# LEDs.net
KiCad netlist of a schematic drawn in Altium Designer
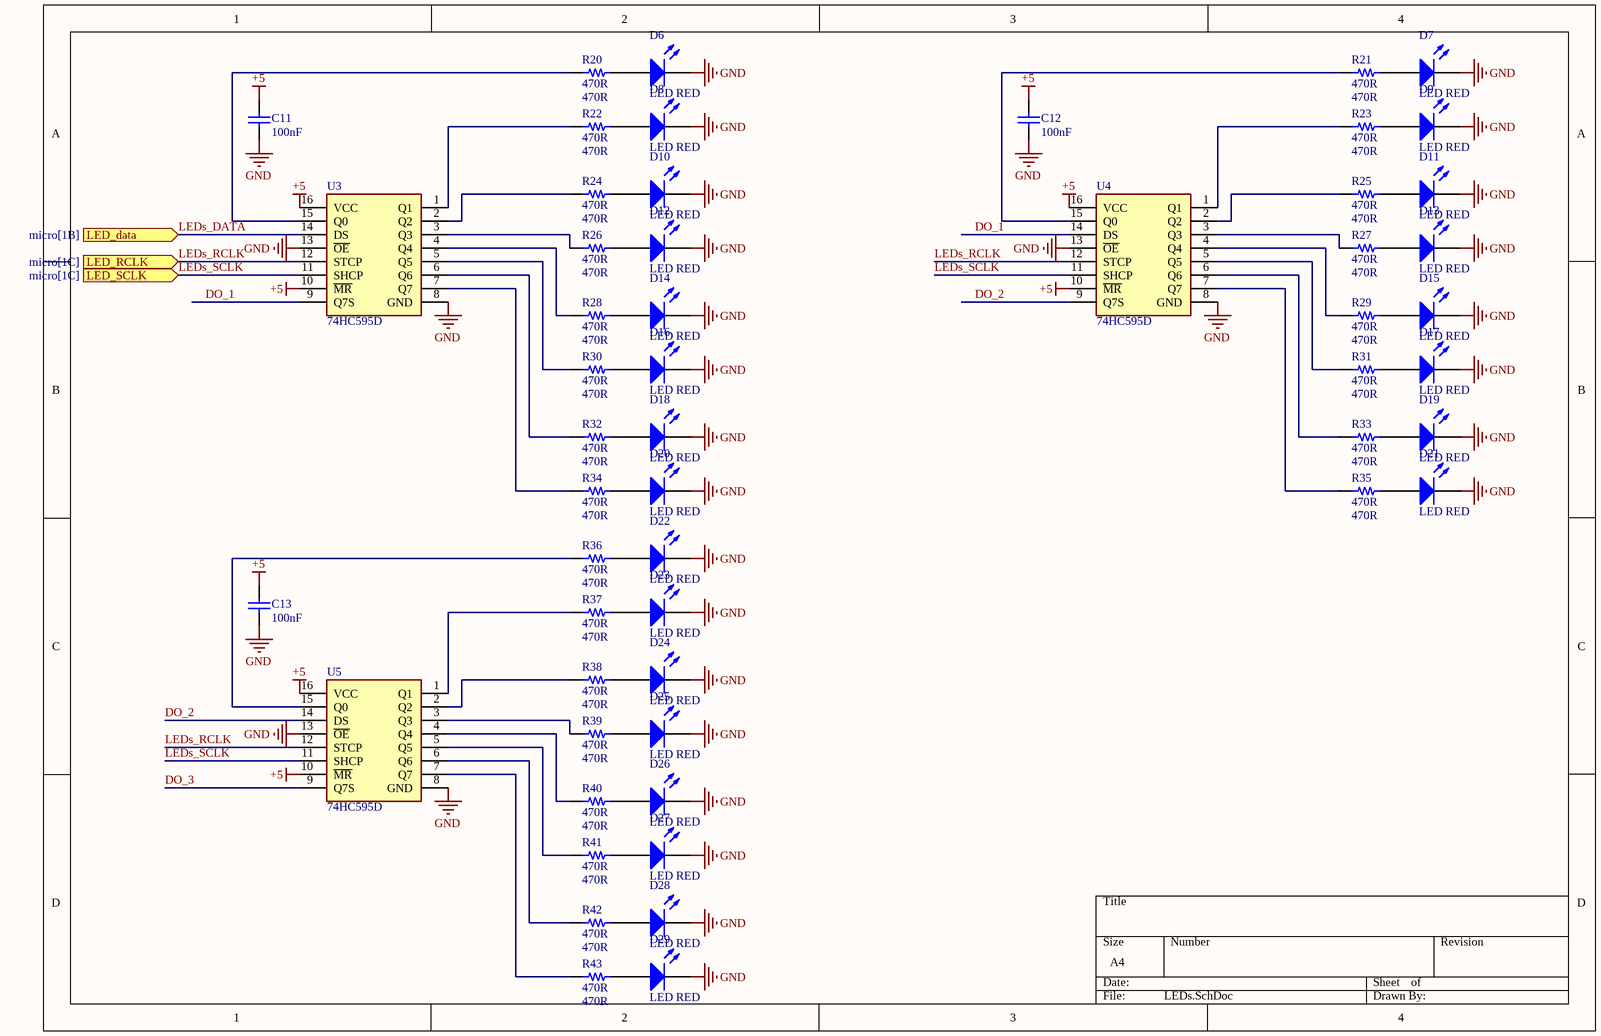
[diagram p0: LEDs.SchDoc]

(export (version "E")
  (design (tool "Eeschema 10.0.6"))
  (components
    (comp (ref "C11")
      (value "100nF")
      (footprint "SMD_CAP_0805")
      (description "CAP SMD 0805")
      (fields (field (name "PUBLISHER") "Altium Limited"))
      (libsource (lib "Miscellaneous Devices") (part "Cap"))
    )
    (comp (ref "C12")
      (value "100nF")
      (footprint "SMD_CAP_0805")
      (description "CAP SMD 0805")
      (fields (field (name "PUBLISHER") "Altium Limited"))
      (libsource (lib "Miscellaneous Devices") (part "Cap"))
    )
    (comp (ref "C13")
      (value "100nF")
      (footprint "SMD_CAP_0805")
      (description "CAP SMD 0805")
      (fields (field (name "PUBLISHER") "Altium Limited"))
      (libsource (lib "Miscellaneous Devices") (part "Cap"))
    )
    (comp (ref "D6")
      (value "LED RED")
      (footprint "LED_0805 G")
      (description "LED SMD 0805 RED")
      (fields (field (name "PUBLISHER") "Altium Limited"))
      (libsource (lib "Miscellaneous Devices") (part "LED0"))
    )
    (comp (ref "D7")
      (value "LED RED")
      (footprint "LED_0805 G")
      (description "LED SMD 0805 RED")
      (fields (field (name "PUBLISHER") "Altium Limited"))
      (libsource (lib "Miscellaneous Devices") (part "LED0"))
    )
    (comp (ref "D8")
      (value "LED RED")
      (footprint "LED_0805 G")
      (description "LED SMD 0805 RED")
      (fields (field (name "PUBLISHER") "Altium Limited"))
      (libsource (lib "Miscellaneous Devices") (part "LED0"))
    )
    (comp (ref "D9")
      (value "LED RED")
      (footprint "LED_0805 G")
      (description "LED SMD 0805 RED")
      (fields (field (name "PUBLISHER") "Altium Limited"))
      (libsource (lib "Miscellaneous Devices") (part "LED0"))
    )
    (comp (ref "D10")
      (value "LED RED")
      (footprint "LED_0805 G")
      (description "LED SMD 0805 RED")
      (fields (field (name "PUBLISHER") "Altium Limited"))
      (libsource (lib "Miscellaneous Devices") (part "LED0"))
    )
    (comp (ref "D11")
      (value "LED RED")
      (footprint "LED_0805 G")
      (description "LED SMD 0805 RED")
      (fields (field (name "PUBLISHER") "Altium Limited"))
      (libsource (lib "Miscellaneous Devices") (part "LED0"))
    )
    (comp (ref "D12")
      (value "LED RED")
      (footprint "LED_0805 G")
      (description "LED SMD 0805 RED")
      (fields (field (name "PUBLISHER") "Altium Limited"))
      (libsource (lib "Miscellaneous Devices") (part "LED0"))
    )
    (comp (ref "D13")
      (value "LED RED")
      (footprint "LED_0805 G")
      (description "LED SMD 0805 RED")
      (fields (field (name "PUBLISHER") "Altium Limited"))
      (libsource (lib "Miscellaneous Devices") (part "LED0"))
    )
    (comp (ref "D14")
      (value "LED RED")
      (footprint "LED_0805 G")
      (description "LED SMD 0805 RED")
      (fields (field (name "PUBLISHER") "Altium Limited"))
      (libsource (lib "Miscellaneous Devices") (part "LED0"))
    )
    (comp (ref "D15")
      (value "LED RED")
      (footprint "LED_0805 G")
      (description "LED SMD 0805 RED")
      (fields (field (name "PUBLISHER") "Altium Limited"))
      (libsource (lib "Miscellaneous Devices") (part "LED0"))
    )
    (comp (ref "D16")
      (value "LED RED")
      (footprint "LED_0805 G")
      (description "LED SMD 0805 RED")
      (fields (field (name "PUBLISHER") "Altium Limited"))
      (libsource (lib "Miscellaneous Devices") (part "LED0"))
    )
    (comp (ref "D17")
      (value "LED RED")
      (footprint "LED_0805 G")
      (description "LED SMD 0805 RED")
      (fields (field (name "PUBLISHER") "Altium Limited"))
      (libsource (lib "Miscellaneous Devices") (part "LED0"))
    )
    (comp (ref "D18")
      (value "LED RED")
      (footprint "LED_0805 G")
      (description "LED SMD 0805 RED")
      (fields (field (name "PUBLISHER") "Altium Limited"))
      (libsource (lib "Miscellaneous Devices") (part "LED0"))
    )
    (comp (ref "D19")
      (value "LED RED")
      (footprint "LED_0805 G")
      (description "LED SMD 0805 RED")
      (fields (field (name "PUBLISHER") "Altium Limited"))
      (libsource (lib "Miscellaneous Devices") (part "LED0"))
    )
    (comp (ref "D20")
      (value "LED RED")
      (footprint "LED_0805 G")
      (description "LED SMD 0805 RED")
      (fields (field (name "PUBLISHER") "Altium Limited"))
      (libsource (lib "Miscellaneous Devices") (part "LED0"))
    )
    (comp (ref "D21")
      (value "LED RED")
      (footprint "LED_0805 G")
      (description "LED SMD 0805 RED")
      (fields (field (name "PUBLISHER") "Altium Limited"))
      (libsource (lib "Miscellaneous Devices") (part "LED0"))
    )
    (comp (ref "D22")
      (value "LED RED")
      (footprint "LED_0805 G")
      (description "LED SMD 0805 RED")
      (fields (field (name "PUBLISHER") "Altium Limited"))
      (libsource (lib "Miscellaneous Devices") (part "LED0"))
    )
    (comp (ref "D23")
      (value "LED RED")
      (footprint "LED_0805 G")
      (description "LED SMD 0805 RED")
      (fields (field (name "PUBLISHER") "Altium Limited"))
      (libsource (lib "Miscellaneous Devices") (part "LED0"))
    )
    (comp (ref "D24")
      (value "LED RED")
      (footprint "LED_0805 G")
      (description "LED SMD 0805 RED")
      (fields (field (name "PUBLISHER") "Altium Limited"))
      (libsource (lib "Miscellaneous Devices") (part "LED0"))
    )
    (comp (ref "D25")
      (value "LED RED")
      (footprint "LED_0805 G")
      (description "LED SMD 0805 RED")
      (fields (field (name "PUBLISHER") "Altium Limited"))
      (libsource (lib "Miscellaneous Devices") (part "LED0"))
    )
    (comp (ref "D26")
      (value "LED RED")
      (footprint "LED_0805 G")
      (description "LED SMD 0805 RED")
      (fields (field (name "PUBLISHER") "Altium Limited"))
      (libsource (lib "Miscellaneous Devices") (part "LED0"))
    )
    (comp (ref "D27")
      (value "LED RED")
      (footprint "LED_0805 G")
      (description "LED SMD 0805 RED")
      (fields (field (name "PUBLISHER") "Altium Limited"))
      (libsource (lib "Miscellaneous Devices") (part "LED0"))
    )
    (comp (ref "D28")
      (value "LED RED")
      (footprint "LED_0805 G")
      (description "LED SMD 0805 RED")
      (fields (field (name "PUBLISHER") "Altium Limited"))
      (libsource (lib "Miscellaneous Devices") (part "LED0"))
    )
    (comp (ref "D29")
      (value "LED RED")
      (footprint "LED_0805 G")
      (description "LED SMD 0805 RED")
      (fields (field (name "PUBLISHER") "Altium Limited"))
      (libsource (lib "Miscellaneous Devices") (part "LED0"))
    )
    (comp (ref "R20")
      (value "470R")
      (footprint "RES0805")
      (description "RES SMD 0603")
      (fields (field (name "PART NUMBER") "RCS0805100KFKEA") (field (name "ALTIUM_VALUE") "470R"))
      (libsource (lib "lamp control-ver2") (part "Resistor"))
    )
    (comp (ref "R21")
      (value "470R")
      (footprint "RES0805")
      (description "RES SMD 0603")
      (fields (field (name "PART NUMBER") "RCS0805100KFKEA") (field (name "ALTIUM_VALUE") "470R"))
      (libsource (lib "lamp control-ver2") (part "Resistor"))
    )
    (comp (ref "R22")
      (value "470R")
      (footprint "RES0805")
      (description "RES SMD 0603")
      (fields (field (name "PART NUMBER") "RCS0805100KFKEA") (field (name "ALTIUM_VALUE") "470R"))
      (libsource (lib "lamp control-ver2") (part "Resistor"))
    )
    (comp (ref "R23")
      (value "470R")
      (footprint "RES0805")
      (description "RES SMD 0603")
      (fields (field (name "PART NUMBER") "RCS0805100KFKEA") (field (name "ALTIUM_VALUE") "470R"))
      (libsource (lib "lamp control-ver2") (part "Resistor"))
    )
    (comp (ref "R24")
      (value "470R")
      (footprint "RES0805")
      (description "RES SMD 0603")
      (fields (field (name "PART NUMBER") "RCS0805100KFKEA") (field (name "ALTIUM_VALUE") "470R"))
      (libsource (lib "lamp control-ver2") (part "Resistor"))
    )
    (comp (ref "R25")
      (value "470R")
      (footprint "RES0805")
      (description "RES SMD 0603")
      (fields (field (name "PART NUMBER") "RCS0805100KFKEA") (field (name "ALTIUM_VALUE") "470R"))
      (libsource (lib "lamp control-ver2") (part "Resistor"))
    )
    (comp (ref "R26")
      (value "470R")
      (footprint "RES0805")
      (description "RES SMD 0603")
      (fields (field (name "PART NUMBER") "RCS0805100KFKEA") (field (name "ALTIUM_VALUE") "470R"))
      (libsource (lib "lamp control-ver2") (part "Resistor"))
    )
    (comp (ref "R27")
      (value "470R")
      (footprint "RES0805")
      (description "RES SMD 0603")
      (fields (field (name "PART NUMBER") "RCS0805100KFKEA") (field (name "ALTIUM_VALUE") "470R"))
      (libsource (lib "lamp control-ver2") (part "Resistor"))
    )
    (comp (ref "R28")
      (value "470R")
      (footprint "RES0805")
      (description "RES SMD 0603")
      (fields (field (name "PART NUMBER") "RCS0805100KFKEA") (field (name "ALTIUM_VALUE") "470R"))
      (libsource (lib "lamp control-ver2") (part "Resistor"))
    )
    (comp (ref "R29")
      (value "470R")
      (footprint "RES0805")
      (description "RES SMD 0603")
      (fields (field (name "PART NUMBER") "RCS0805100KFKEA") (field (name "ALTIUM_VALUE") "470R"))
      (libsource (lib "lamp control-ver2") (part "Resistor"))
    )
    (comp (ref "R30")
      (value "470R")
      (footprint "RES0805")
      (description "RES SMD 0603")
      (fields (field (name "PART NUMBER") "RCS0805100KFKEA") (field (name "ALTIUM_VALUE") "470R"))
      (libsource (lib "lamp control-ver2") (part "Resistor"))
    )
    (comp (ref "R31")
      (value "470R")
      (footprint "RES0805")
      (description "RES SMD 0603")
      (fields (field (name "PART NUMBER") "RCS0805100KFKEA") (field (name "ALTIUM_VALUE") "470R"))
      (libsource (lib "lamp control-ver2") (part "Resistor"))
    )
    (comp (ref "R32")
      (value "470R")
      (footprint "RES0805")
      (description "RES SMD 0603")
      (fields (field (name "PART NUMBER") "RCS0805100KFKEA") (field (name "ALTIUM_VALUE") "470R"))
      (libsource (lib "lamp control-ver2") (part "Resistor"))
    )
    (comp (ref "R33")
      (value "470R")
      (footprint "RES0805")
      (description "RES SMD 0603")
      (fields (field (name "PART NUMBER") "RCS0805100KFKEA") (field (name "ALTIUM_VALUE") "470R"))
      (libsource (lib "lamp control-ver2") (part "Resistor"))
    )
    (comp (ref "R34")
      (value "470R")
      (footprint "RES0805")
      (description "RES SMD 0603")
      (fields (field (name "PART NUMBER") "RCS0805100KFKEA") (field (name "ALTIUM_VALUE") "470R"))
      (libsource (lib "lamp control-ver2") (part "Resistor"))
    )
    (comp (ref "R35")
      (value "470R")
      (footprint "RES0805")
      (description "RES SMD 0603")
      (fields (field (name "PART NUMBER") "RCS0805100KFKEA") (field (name "ALTIUM_VALUE") "470R"))
      (libsource (lib "lamp control-ver2") (part "Resistor"))
    )
    (comp (ref "R36")
      (value "470R")
      (footprint "RES0805")
      (description "RES SMD 0603")
      (fields (field (name "PART NUMBER") "RCS0805100KFKEA") (field (name "ALTIUM_VALUE") "470R"))
      (libsource (lib "lamp control-ver2") (part "Resistor"))
    )
    (comp (ref "R37")
      (value "470R")
      (footprint "RES0805")
      (description "RES SMD 0603")
      (fields (field (name "PART NUMBER") "RCS0805100KFKEA") (field (name "ALTIUM_VALUE") "470R"))
      (libsource (lib "lamp control-ver2") (part "Resistor"))
    )
    (comp (ref "R38")
      (value "470R")
      (footprint "RES0805")
      (description "RES SMD 0603")
      (fields (field (name "PART NUMBER") "RCS0805100KFKEA") (field (name "ALTIUM_VALUE") "470R"))
      (libsource (lib "lamp control-ver2") (part "Resistor"))
    )
    (comp (ref "R39")
      (value "470R")
      (footprint "RES0805")
      (description "RES SMD 0603")
      (fields (field (name "PART NUMBER") "RCS0805100KFKEA") (field (name "ALTIUM_VALUE") "470R"))
      (libsource (lib "lamp control-ver2") (part "Resistor"))
    )
    (comp (ref "R40")
      (value "470R")
      (footprint "RES0805")
      (description "RES SMD 0603")
      (fields (field (name "PART NUMBER") "RCS0805100KFKEA") (field (name "ALTIUM_VALUE") "470R"))
      (libsource (lib "lamp control-ver2") (part "Resistor"))
    )
    (comp (ref "R41")
      (value "470R")
      (footprint "RES0805")
      (description "RES SMD 0603")
      (fields (field (name "PART NUMBER") "RCS0805100KFKEA") (field (name "ALTIUM_VALUE") "470R"))
      (libsource (lib "lamp control-ver2") (part "Resistor"))
    )
    (comp (ref "R42")
      (value "470R")
      (footprint "RES0805")
      (description "RES SMD 0603")
      (fields (field (name "PART NUMBER") "RCS0805100KFKEA") (field (name "ALTIUM_VALUE") "470R"))
      (libsource (lib "lamp control-ver2") (part "Resistor"))
    )
    (comp (ref "R43")
      (value "470R")
      (footprint "RES0805")
      (description "RES SMD 0603")
      (fields (field (name "PART NUMBER") "RCS0805100KFKEA") (field (name "ALTIUM_VALUE") "470R"))
      (libsource (lib "lamp control-ver2") (part "Resistor"))
    )
    (comp (ref "U3")
      (value "74HC595D")
      (footprint "SOIC127P600X175-16N")
      (description "74HC595 SMD")
      (libsource (lib "*") (part "74HC595D"))
    )
    (comp (ref "U4")
      (value "74HC595D")
      (footprint "SOIC127P600X175-16N")
      (description "74HC595 SMD")
      (libsource (lib "*") (part "74HC595D"))
    )
    (comp (ref "U5")
      (value "74HC595D")
      (footprint "SOIC127P600X175-16N")
      (description "74HC595 SMD")
      (libsource (lib "*") (part "74HC595D"))
    )
  )
  (nets
    (net (code "1") (name "+5") (class "Default")
      (node (ref "C11") (pin "2") (pinfunction "2_2") (pintype "passive"))
      (node (ref "C12") (pin "2") (pinfunction "2_2") (pintype "passive"))
      (node (ref "C13") (pin "2") (pinfunction "2_2") (pintype "passive"))
      (node (ref "U3") (pin "10") (pinfunction "~{MR}_10") (pintype "passive"))
      (node (ref "U3") (pin "16") (pinfunction "VCC_16") (pintype "passive"))
      (node (ref "U4") (pin "10") (pinfunction "~{MR}_10") (pintype "passive"))
      (node (ref "U4") (pin "16") (pinfunction "VCC_16") (pintype "passive"))
      (node (ref "U5") (pin "10") (pinfunction "~{MR}_10") (pintype "passive"))
      (node (ref "U5") (pin "16") (pinfunction "VCC_16") (pintype "passive"))
    )
    (net (code "2") (name "/DO_1") (class "Default")
      (node (ref "U3") (pin "9") (pinfunction "Q7S_9") (pintype "passive"))
      (node (ref "U4") (pin "14") (pinfunction "DS_14") (pintype "passive"))
    )
    (net (code "3") (name "/DO_2") (class "Default")
      (node (ref "U4") (pin "9") (pinfunction "Q7S_9") (pintype "passive"))
      (node (ref "U5") (pin "14") (pinfunction "DS_14") (pintype "passive"))
    )
    (net (code "4") (name "/DO_3") (class "Default")
      (node (ref "U5") (pin "9") (pinfunction "Q7S_9") (pintype "passive"))
    )
    (net (code "5") (name "/LEDs_DATA") (class "Default")
      (node (ref "U3") (pin "14") (pinfunction "DS_14") (pintype "passive"))
    )
    (net (code "6") (name "/LEDs_RCLK") (class "Default")
      (node (ref "U3") (pin "12") (pinfunction "STCP_12") (pintype "passive"))
      (node (ref "U4") (pin "12") (pinfunction "STCP_12") (pintype "passive"))
      (node (ref "U5") (pin "12") (pinfunction "STCP_12") (pintype "passive"))
    )
    (net (code "7") (name "/LEDs_SCLK") (class "Default")
      (node (ref "U3") (pin "11") (pinfunction "SHCP_11") (pintype "passive"))
      (node (ref "U4") (pin "11") (pinfunction "SHCP_11") (pintype "passive"))
      (node (ref "U5") (pin "11") (pinfunction "SHCP_11") (pintype "passive"))
    )
    (net (code "8") (name "GND") (class "Default")
      (node (ref "C11") (pin "1") (pinfunction "1_1") (pintype "passive"))
      (node (ref "C12") (pin "1") (pinfunction "1_1") (pintype "passive"))
      (node (ref "C13") (pin "1") (pinfunction "1_1") (pintype "passive"))
      (node (ref "D10") (pin "2") (pinfunction "K_2") (pintype "passive"))
      (node (ref "D11") (pin "2") (pinfunction "K_2") (pintype "passive"))
      (node (ref "D12") (pin "2") (pinfunction "K_2") (pintype "passive"))
      (node (ref "D13") (pin "2") (pinfunction "K_2") (pintype "passive"))
      (node (ref "D14") (pin "2") (pinfunction "K_2") (pintype "passive"))
      (node (ref "D15") (pin "2") (pinfunction "K_2") (pintype "passive"))
      (node (ref "D16") (pin "2") (pinfunction "K_2") (pintype "passive"))
      (node (ref "D17") (pin "2") (pinfunction "K_2") (pintype "passive"))
      (node (ref "D18") (pin "2") (pinfunction "K_2") (pintype "passive"))
      (node (ref "D19") (pin "2") (pinfunction "K_2") (pintype "passive"))
      (node (ref "D20") (pin "2") (pinfunction "K_2") (pintype "passive"))
      (node (ref "D21") (pin "2") (pinfunction "K_2") (pintype "passive"))
      (node (ref "D22") (pin "2") (pinfunction "K_2") (pintype "passive"))
      (node (ref "D23") (pin "2") (pinfunction "K_2") (pintype "passive"))
      (node (ref "D24") (pin "2") (pinfunction "K_2") (pintype "passive"))
      (node (ref "D25") (pin "2") (pinfunction "K_2") (pintype "passive"))
      (node (ref "D26") (pin "2") (pinfunction "K_2") (pintype "passive"))
      (node (ref "D27") (pin "2") (pinfunction "K_2") (pintype "passive"))
      (node (ref "D28") (pin "2") (pinfunction "K_2") (pintype "passive"))
      (node (ref "D29") (pin "2") (pinfunction "K_2") (pintype "passive"))
      (node (ref "D6") (pin "2") (pinfunction "K_2") (pintype "passive"))
      (node (ref "D7") (pin "2") (pinfunction "K_2") (pintype "passive"))
      (node (ref "D8") (pin "2") (pinfunction "K_2") (pintype "passive"))
      (node (ref "D9") (pin "2") (pinfunction "K_2") (pintype "passive"))
      (node (ref "U3") (pin "13") (pinfunction "~{OE}_13") (pintype "passive"))
      (node (ref "U3") (pin "8") (pinfunction "GND_8") (pintype "passive"))
      (node (ref "U4") (pin "13") (pinfunction "~{OE}_13") (pintype "passive"))
      (node (ref "U4") (pin "8") (pinfunction "GND_8") (pintype "passive"))
      (node (ref "U5") (pin "13") (pinfunction "~{OE}_13") (pintype "passive"))
      (node (ref "U5") (pin "8") (pinfunction "GND_8") (pintype "passive"))
    )
    (net (code "9") (name "Net-(D6-A)") (class "Default")
      (node (ref "D6") (pin "1") (pinfunction "A_1") (pintype "passive"))
      (node (ref "R20") (pin "1") (pinfunction "1_1") (pintype "passive"))
    )
    (net (code "10") (name "Net-(D7-A)") (class "Default")
      (node (ref "D7") (pin "1") (pinfunction "A_1") (pintype "passive"))
      (node (ref "R21") (pin "1") (pinfunction "1_1") (pintype "passive"))
    )
    (net (code "11") (name "Net-(D8-A)") (class "Default")
      (node (ref "D8") (pin "1") (pinfunction "A_1") (pintype "passive"))
      (node (ref "R22") (pin "1") (pinfunction "1_1") (pintype "passive"))
    )
    (net (code "12") (name "Net-(D9-A)") (class "Default")
      (node (ref "D9") (pin "1") (pinfunction "A_1") (pintype "passive"))
      (node (ref "R23") (pin "1") (pinfunction "1_1") (pintype "passive"))
    )
    (net (code "13") (name "Net-(D10-A)") (class "Default")
      (node (ref "D10") (pin "1") (pinfunction "A_1") (pintype "passive"))
      (node (ref "R24") (pin "1") (pinfunction "1_1") (pintype "passive"))
    )
    (net (code "14") (name "Net-(D11-A)") (class "Default")
      (node (ref "D11") (pin "1") (pinfunction "A_1") (pintype "passive"))
      (node (ref "R25") (pin "1") (pinfunction "1_1") (pintype "passive"))
    )
    (net (code "15") (name "Net-(D12-A)") (class "Default")
      (node (ref "D12") (pin "1") (pinfunction "A_1") (pintype "passive"))
      (node (ref "R26") (pin "1") (pinfunction "1_1") (pintype "passive"))
    )
    (net (code "16") (name "Net-(D13-A)") (class "Default")
      (node (ref "D13") (pin "1") (pinfunction "A_1") (pintype "passive"))
      (node (ref "R27") (pin "1") (pinfunction "1_1") (pintype "passive"))
    )
    (net (code "17") (name "Net-(D14-A)") (class "Default")
      (node (ref "D14") (pin "1") (pinfunction "A_1") (pintype "passive"))
      (node (ref "R28") (pin "1") (pinfunction "1_1") (pintype "passive"))
    )
    (net (code "18") (name "Net-(D15-A)") (class "Default")
      (node (ref "D15") (pin "1") (pinfunction "A_1") (pintype "passive"))
      (node (ref "R29") (pin "1") (pinfunction "1_1") (pintype "passive"))
    )
    (net (code "19") (name "Net-(D16-A)") (class "Default")
      (node (ref "D16") (pin "1") (pinfunction "A_1") (pintype "passive"))
      (node (ref "R30") (pin "1") (pinfunction "1_1") (pintype "passive"))
    )
    (net (code "20") (name "Net-(D17-A)") (class "Default")
      (node (ref "D17") (pin "1") (pinfunction "A_1") (pintype "passive"))
      (node (ref "R31") (pin "1") (pinfunction "1_1") (pintype "passive"))
    )
    (net (code "21") (name "Net-(D18-A)") (class "Default")
      (node (ref "D18") (pin "1") (pinfunction "A_1") (pintype "passive"))
      (node (ref "R32") (pin "1") (pinfunction "1_1") (pintype "passive"))
    )
    (net (code "22") (name "Net-(D19-A)") (class "Default")
      (node (ref "D19") (pin "1") (pinfunction "A_1") (pintype "passive"))
      (node (ref "R33") (pin "1") (pinfunction "1_1") (pintype "passive"))
    )
    (net (code "23") (name "Net-(D20-A)") (class "Default")
      (node (ref "D20") (pin "1") (pinfunction "A_1") (pintype "passive"))
      (node (ref "R34") (pin "1") (pinfunction "1_1") (pintype "passive"))
    )
    (net (code "24") (name "Net-(D21-A)") (class "Default")
      (node (ref "D21") (pin "1") (pinfunction "A_1") (pintype "passive"))
      (node (ref "R35") (pin "1") (pinfunction "1_1") (pintype "passive"))
    )
    (net (code "25") (name "Net-(D22-A)") (class "Default")
      (node (ref "D22") (pin "1") (pinfunction "A_1") (pintype "passive"))
      (node (ref "R36") (pin "1") (pinfunction "1_1") (pintype "passive"))
    )
    (net (code "26") (name "Net-(D23-A)") (class "Default")
      (node (ref "D23") (pin "1") (pinfunction "A_1") (pintype "passive"))
      (node (ref "R37") (pin "1") (pinfunction "1_1") (pintype "passive"))
    )
    (net (code "27") (name "Net-(D24-A)") (class "Default")
      (node (ref "D24") (pin "1") (pinfunction "A_1") (pintype "passive"))
      (node (ref "R38") (pin "1") (pinfunction "1_1") (pintype "passive"))
    )
    (net (code "28") (name "Net-(D25-A)") (class "Default")
      (node (ref "D25") (pin "1") (pinfunction "A_1") (pintype "passive"))
      (node (ref "R39") (pin "1") (pinfunction "1_1") (pintype "passive"))
    )
    (net (code "29") (name "Net-(D26-A)") (class "Default")
      (node (ref "D26") (pin "1") (pinfunction "A_1") (pintype "passive"))
      (node (ref "R40") (pin "1") (pinfunction "1_1") (pintype "passive"))
    )
    (net (code "30") (name "Net-(D27-A)") (class "Default")
      (node (ref "D27") (pin "1") (pinfunction "A_1") (pintype "passive"))
      (node (ref "R41") (pin "1") (pinfunction "1_1") (pintype "passive"))
    )
    (net (code "31") (name "Net-(D28-A)") (class "Default")
      (node (ref "D28") (pin "1") (pinfunction "A_1") (pintype "passive"))
      (node (ref "R42") (pin "1") (pinfunction "1_1") (pintype "passive"))
    )
    (net (code "32") (name "Net-(D29-A)") (class "Default")
      (node (ref "D29") (pin "1") (pinfunction "A_1") (pintype "passive"))
      (node (ref "R43") (pin "1") (pinfunction "1_1") (pintype "passive"))
    )
    (net (code "33") (name "Net-(U3-Q0)") (class "Default")
      (node (ref "R20") (pin "2") (pinfunction "2_2") (pintype "passive"))
      (node (ref "U3") (pin "15") (pinfunction "Q0_15") (pintype "passive"))
    )
    (net (code "34") (name "Net-(U3-Q1)") (class "Default")
      (node (ref "R22") (pin "2") (pinfunction "2_2") (pintype "passive"))
      (node (ref "U3") (pin "1") (pinfunction "Q1_1") (pintype "passive"))
    )
    (net (code "35") (name "Net-(U3-Q2)") (class "Default")
      (node (ref "R24") (pin "2") (pinfunction "2_2") (pintype "passive"))
      (node (ref "U3") (pin "2") (pinfunction "Q2_2") (pintype "passive"))
    )
    (net (code "36") (name "Net-(U3-Q3)") (class "Default")
      (node (ref "R26") (pin "2") (pinfunction "2_2") (pintype "passive"))
      (node (ref "U3") (pin "3") (pinfunction "Q3_3") (pintype "passive"))
    )
    (net (code "37") (name "Net-(U3-Q4)") (class "Default")
      (node (ref "R28") (pin "2") (pinfunction "2_2") (pintype "passive"))
      (node (ref "U3") (pin "4") (pinfunction "Q4_4") (pintype "passive"))
    )
    (net (code "38") (name "Net-(U3-Q5)") (class "Default")
      (node (ref "R30") (pin "2") (pinfunction "2_2") (pintype "passive"))
      (node (ref "U3") (pin "5") (pinfunction "Q5_5") (pintype "passive"))
    )
    (net (code "39") (name "Net-(U3-Q6)") (class "Default")
      (node (ref "R32") (pin "2") (pinfunction "2_2") (pintype "passive"))
      (node (ref "U3") (pin "6") (pinfunction "Q6_6") (pintype "passive"))
    )
    (net (code "40") (name "Net-(U3-Q7)") (class "Default")
      (node (ref "R34") (pin "2") (pinfunction "2_2") (pintype "passive"))
      (node (ref "U3") (pin "7") (pinfunction "Q7_7") (pintype "passive"))
    )
    (net (code "41") (name "Net-(U4-Q0)") (class "Default")
      (node (ref "R21") (pin "2") (pinfunction "2_2") (pintype "passive"))
      (node (ref "U4") (pin "15") (pinfunction "Q0_15") (pintype "passive"))
    )
    (net (code "42") (name "Net-(U4-Q1)") (class "Default")
      (node (ref "R23") (pin "2") (pinfunction "2_2") (pintype "passive"))
      (node (ref "U4") (pin "1") (pinfunction "Q1_1") (pintype "passive"))
    )
    (net (code "43") (name "Net-(U4-Q2)") (class "Default")
      (node (ref "R25") (pin "2") (pinfunction "2_2") (pintype "passive"))
      (node (ref "U4") (pin "2") (pinfunction "Q2_2") (pintype "passive"))
    )
    (net (code "44") (name "Net-(U4-Q3)") (class "Default")
      (node (ref "R27") (pin "2") (pinfunction "2_2") (pintype "passive"))
      (node (ref "U4") (pin "3") (pinfunction "Q3_3") (pintype "passive"))
    )
    (net (code "45") (name "Net-(U4-Q4)") (class "Default")
      (node (ref "R29") (pin "2") (pinfunction "2_2") (pintype "passive"))
      (node (ref "U4") (pin "4") (pinfunction "Q4_4") (pintype "passive"))
    )
    (net (code "46") (name "Net-(U4-Q5)") (class "Default")
      (node (ref "R31") (pin "2") (pinfunction "2_2") (pintype "passive"))
      (node (ref "U4") (pin "5") (pinfunction "Q5_5") (pintype "passive"))
    )
    (net (code "47") (name "Net-(U4-Q6)") (class "Default")
      (node (ref "R33") (pin "2") (pinfunction "2_2") (pintype "passive"))
      (node (ref "U4") (pin "6") (pinfunction "Q6_6") (pintype "passive"))
    )
    (net (code "48") (name "Net-(U4-Q7)") (class "Default")
      (node (ref "R35") (pin "2") (pinfunction "2_2") (pintype "passive"))
      (node (ref "U4") (pin "7") (pinfunction "Q7_7") (pintype "passive"))
    )
    (net (code "49") (name "Net-(U5-Q0)") (class "Default")
      (node (ref "R36") (pin "2") (pinfunction "2_2") (pintype "passive"))
      (node (ref "U5") (pin "15") (pinfunction "Q0_15") (pintype "passive"))
    )
    (net (code "50") (name "Net-(U5-Q1)") (class "Default")
      (node (ref "R37") (pin "2") (pinfunction "2_2") (pintype "passive"))
      (node (ref "U5") (pin "1") (pinfunction "Q1_1") (pintype "passive"))
    )
    (net (code "51") (name "Net-(U5-Q2)") (class "Default")
      (node (ref "R38") (pin "2") (pinfunction "2_2") (pintype "passive"))
      (node (ref "U5") (pin "2") (pinfunction "Q2_2") (pintype "passive"))
    )
    (net (code "52") (name "Net-(U5-Q3)") (class "Default")
      (node (ref "R39") (pin "2") (pinfunction "2_2") (pintype "passive"))
      (node (ref "U5") (pin "3") (pinfunction "Q3_3") (pintype "passive"))
    )
    (net (code "53") (name "Net-(U5-Q4)") (class "Default")
      (node (ref "R40") (pin "2") (pinfunction "2_2") (pintype "passive"))
      (node (ref "U5") (pin "4") (pinfunction "Q4_4") (pintype "passive"))
    )
    (net (code "54") (name "Net-(U5-Q5)") (class "Default")
      (node (ref "R41") (pin "2") (pinfunction "2_2") (pintype "passive"))
      (node (ref "U5") (pin "5") (pinfunction "Q5_5") (pintype "passive"))
    )
    (net (code "55") (name "Net-(U5-Q6)") (class "Default")
      (node (ref "R42") (pin "2") (pinfunction "2_2") (pintype "passive"))
      (node (ref "U5") (pin "6") (pinfunction "Q6_6") (pintype "passive"))
    )
    (net (code "56") (name "Net-(U5-Q7)") (class "Default")
      (node (ref "R43") (pin "2") (pinfunction "2_2") (pintype "passive"))
      (node (ref "U5") (pin "7") (pinfunction "Q7_7") (pintype "passive"))
    )
  )
)
